# esp_thermometer.net
KiCad netlist of a schematic drawn in EAGLE
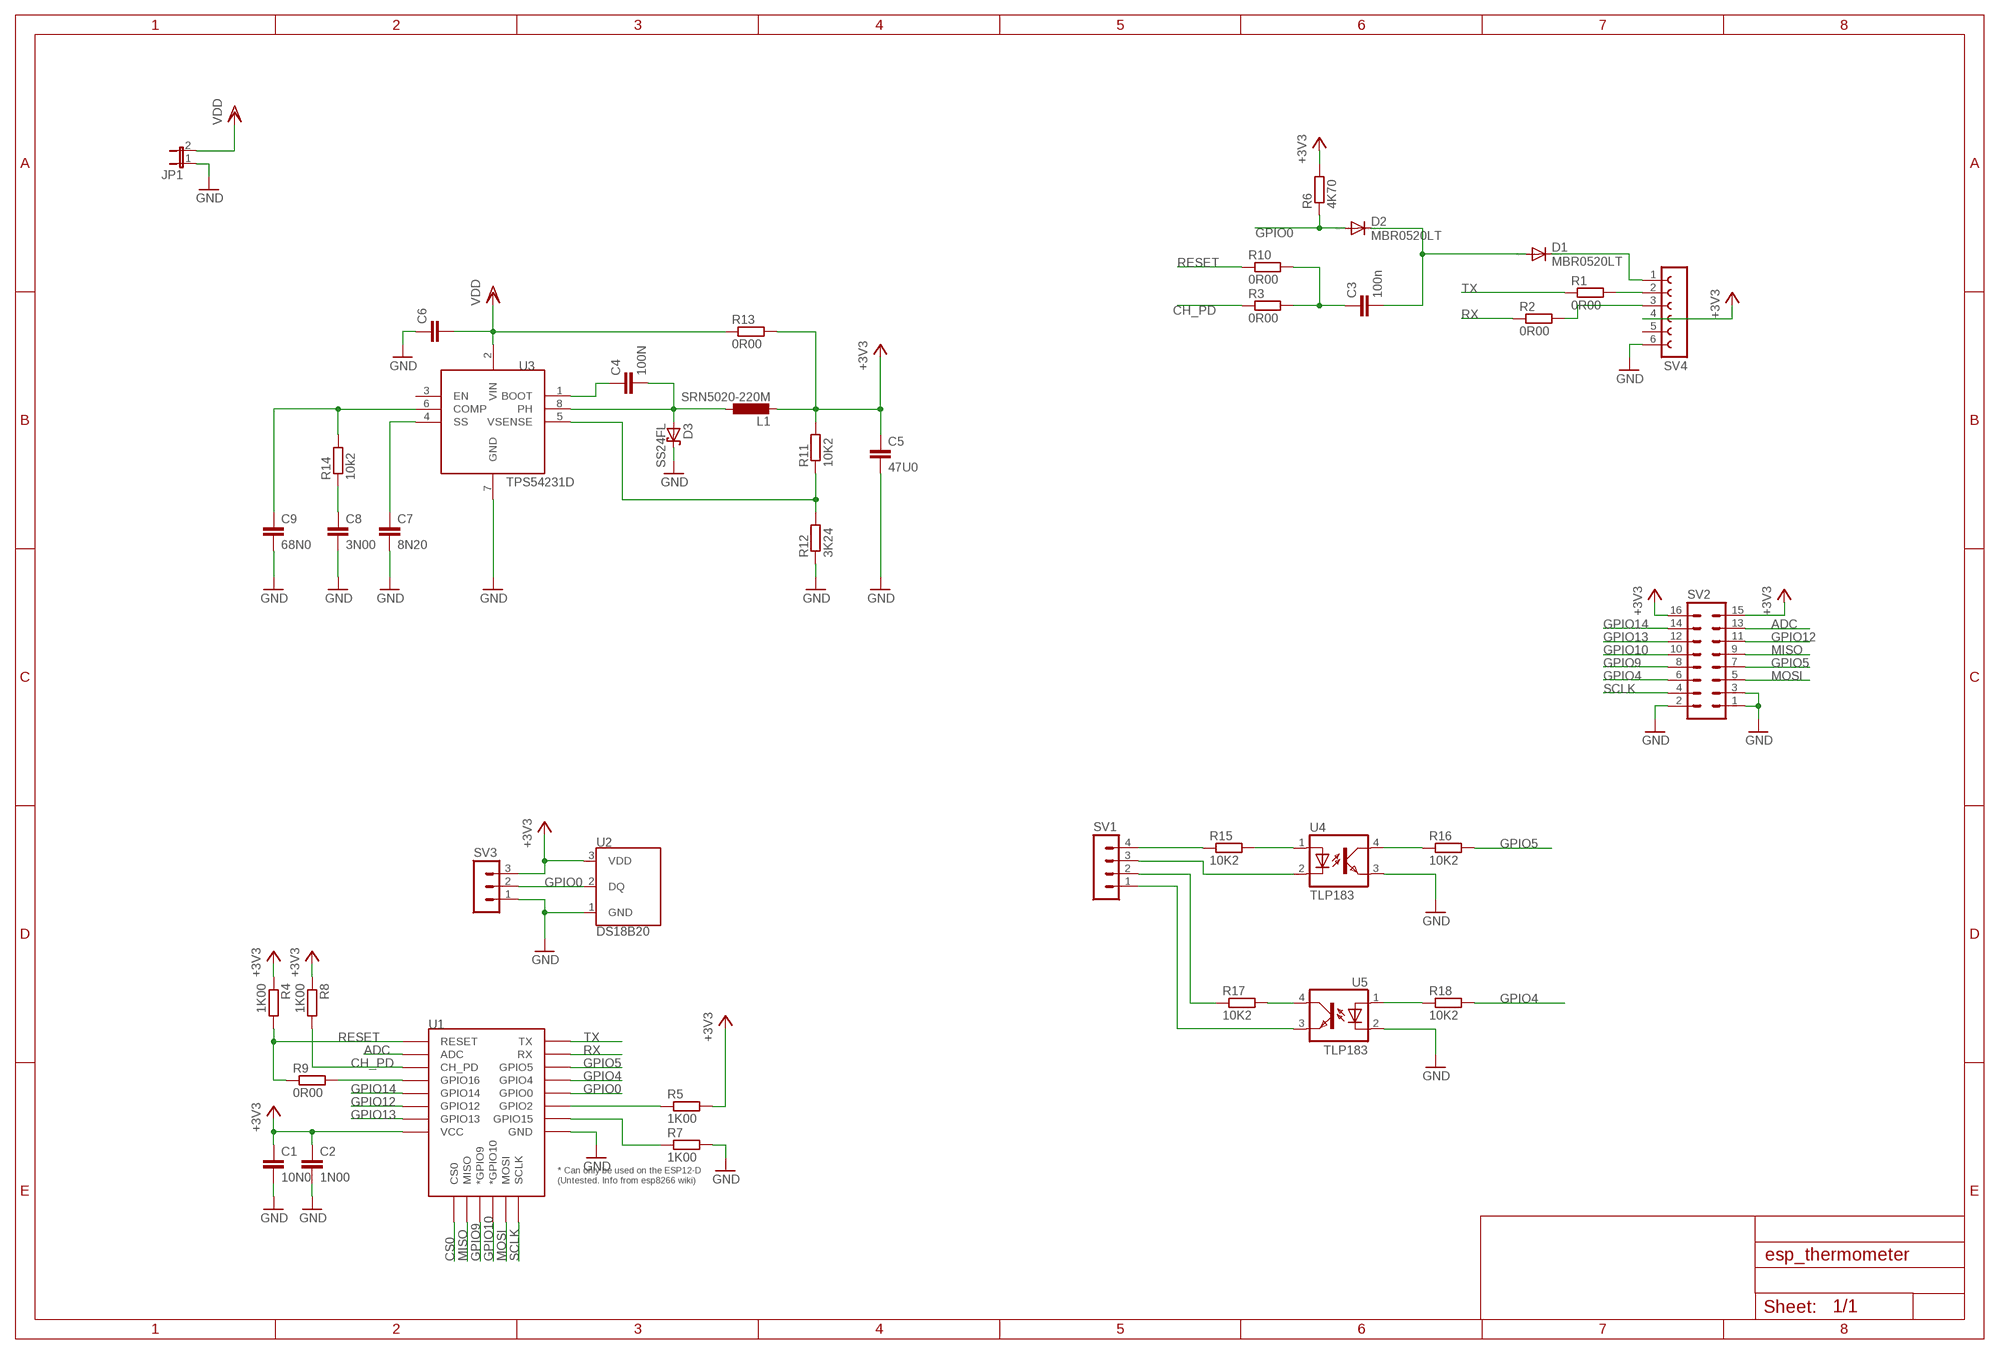
[diagram p0: schematic, sheet 1]

(export (version "E")
  (design (tool "Eeschema 10.0.6"))
  (components
    (comp (ref "C1")
      (value "10N0")
      (footprint "eagle-import:C1206K")
      (libsource (lib "eagle-import") (part "C-EUC1206K"))
    )
    (comp (ref "C2")
      (value "1N00")
      (footprint "eagle-import:C1206K")
      (libsource (lib "eagle-import") (part "C-EUC1206K"))
    )
    (comp (ref "C3")
      (value "100n")
      (footprint "eagle-import:C1206K")
      (libsource (lib "eagle-import") (part "C-EUC1206K"))
    )
    (comp (ref "C4")
      (value "100N")
      (footprint "eagle-import:C0805")
      (libsource (lib "eagle-import") (part "C-EUC0805"))
    )
    (comp (ref "C5")
      (value "47U0")
      (footprint "eagle-import:C1210")
      (libsource (lib "eagle-import") (part "C-EUC1210"))
    )
    (comp (ref "C6")
      (value "C-EUC1210")
      (footprint "eagle-import:C1210")
      (libsource (lib "eagle-import") (part "C-EUC1210"))
    )
    (comp (ref "C7")
      (value "8N20")
      (footprint "eagle-import:C0805")
      (libsource (lib "eagle-import") (part "C-EUC0805"))
    )
    (comp (ref "C8")
      (value "3N00")
      (footprint "eagle-import:C0805")
      (libsource (lib "eagle-import") (part "C-EUC0805"))
    )
    (comp (ref "C9")
      (value "68N0")
      (footprint "eagle-import:C0805")
      (libsource (lib "eagle-import") (part "C-EUC0805"))
    )
    (comp (ref "D1")
      (value "MBR0520LT")
      (footprint "eagle-import:SOD123")
      (libsource (lib "eagle-import") (part "MBR0520LT"))
    )
    (comp (ref "D2")
      (value "MBR0520LT")
      (footprint "eagle-import:SOD123")
      (libsource (lib "eagle-import") (part "MBR0520LT"))
    )
    (comp (ref "D3")
      (value "SS24FL")
      (footprint "eagle-import:SOD-123_MINI-SMA")
      (libsource (lib "eagle-import") (part "SS24FL"))
    )
    (comp (ref "JP1")
      (value "JP1E")
      (footprint "eagle-import:JP1")
      (libsource (lib "eagle-import") (part "JP1E"))
    )
    (comp (ref "L1")
      (value "SRN5020-220M")
      (footprint "eagle-import:L5050")
      (libsource (lib "eagle-import") (part "SRN5020-220M"))
    )
    (comp (ref "R1")
      (value "0R00")
      (footprint "eagle-import:R0805")
      (libsource (lib "eagle-import") (part "R-EU_R0805"))
    )
    (comp (ref "R2")
      (value "0R00")
      (footprint "eagle-import:R0805")
      (libsource (lib "eagle-import") (part "R-EU_R0805"))
    )
    (comp (ref "R3")
      (value "0R00")
      (footprint "eagle-import:R0805")
      (libsource (lib "eagle-import") (part "R-EU_R0805"))
    )
    (comp (ref "R4")
      (value "1K00")
      (footprint "eagle-import:R0805")
      (libsource (lib "eagle-import") (part "R-EU_R0805"))
    )
    (comp (ref "R5")
      (value "1K00")
      (footprint "eagle-import:R0805")
      (libsource (lib "eagle-import") (part "R-EU_R0805"))
    )
    (comp (ref "R6")
      (value "4K70")
      (footprint "eagle-import:R0805")
      (libsource (lib "eagle-import") (part "R-EU_R0805"))
    )
    (comp (ref "R7")
      (value "1K00")
      (footprint "eagle-import:R0805")
      (libsource (lib "eagle-import") (part "R-EU_R0805"))
    )
    (comp (ref "R8")
      (value "1K00")
      (footprint "eagle-import:R0805")
      (libsource (lib "eagle-import") (part "R-EU_R0805"))
    )
    (comp (ref "R9")
      (value "0R00")
      (footprint "eagle-import:R0805")
      (libsource (lib "eagle-import") (part "R-EU_R0805"))
    )
    (comp (ref "R10")
      (value "0R00")
      (footprint "eagle-import:R0805")
      (libsource (lib "eagle-import") (part "R-EU_R0805"))
    )
    (comp (ref "R11")
      (value "10K2")
      (footprint "eagle-import:R0805")
      (libsource (lib "eagle-import") (part "R-EU_R0805"))
    )
    (comp (ref "R12")
      (value "3K24")
      (footprint "eagle-import:R0805")
      (libsource (lib "eagle-import") (part "R-EU_R0805"))
    )
    (comp (ref "R13")
      (value "0R00")
      (footprint "eagle-import:R0805")
      (libsource (lib "eagle-import") (part "R-EU_R0805"))
    )
    (comp (ref "R14")
      (value "10k2")
      (footprint "eagle-import:R0805")
      (libsource (lib "eagle-import") (part "R-EU_R0805"))
    )
    (comp (ref "R15")
      (value "10K2")
      (footprint "eagle-import:R0805")
      (libsource (lib "eagle-import") (part "R-EU_R0805"))
    )
    (comp (ref "R16")
      (value "10K2")
      (footprint "eagle-import:R0805")
      (libsource (lib "eagle-import") (part "R-EU_R0805"))
    )
    (comp (ref "R17")
      (value "10K2")
      (footprint "eagle-import:R0805")
      (libsource (lib "eagle-import") (part "R-EU_R0805"))
    )
    (comp (ref "R18")
      (value "10K2")
      (footprint "eagle-import:R0805")
      (libsource (lib "eagle-import") (part "R-EU_R0805"))
    )
    (comp (ref "SV1")
      (value "MA04-1")
      (footprint "eagle-import:MA04-1")
      (libsource (lib "eagle-import") (part "MA04-1"))
    )
    (comp (ref "SV2")
      (value "MA08-2")
      (footprint "eagle-import:MA08-2")
      (libsource (lib "eagle-import") (part "MA08-2"))
    )
    (comp (ref "SV3")
      (value "MA03-1")
      (footprint "eagle-import:MA03-1")
      (libsource (lib "eagle-import") (part "MA03-1"))
    )
    (comp (ref "SV4")
      (value "FE06-1")
      (footprint "eagle-import:FE06")
      (libsource (lib "eagle-import") (part "FE06-1"))
    )
    (comp (ref "U1")
      (value "ESP12ESMD")
      (footprint "eagle-import:ESP12E-SMD")
      (libsource (lib "eagle-import") (part "ESP12ESMD"))
    )
    (comp (ref "U2")
      (value "DS18B20")
      (footprint "eagle-import:TO-92-AMMO")
      (libsource (lib "eagle-import") (part "DS18B20"))
    )
    (comp (ref "U3")
      (value "TPS54231D")
      (footprint "eagle-import:D0008A")
      (libsource (lib "eagle-import") (part "TPS54231D"))
    )
    (comp (ref "U4")
      (value "TLP183")
      (footprint "eagle-import:MINI-FLAT-4")
      (libsource (lib "eagle-import") (part "TLP183"))
    )
    (comp (ref "U5")
      (value "TLP183")
      (footprint "eagle-import:MINI-FLAT-4")
      (libsource (lib "eagle-import") (part "TLP183"))
    )
  )
  (nets
    (net (code "1") (name "+3V3") (class "Default")
      (node (ref "C1") (pin "1") (pinfunction "1_1") (pintype "passive"))
      (node (ref "C2") (pin "1") (pinfunction "1_1") (pintype "passive"))
      (node (ref "C5") (pin "1") (pinfunction "1_1") (pintype "passive"))
      (node (ref "L1") (pin "2") (pinfunction "2_2") (pintype "passive"))
      (node (ref "R11") (pin "2") (pinfunction "2_2") (pintype "passive"))
      (node (ref "R13") (pin "2") (pinfunction "2_2") (pintype "passive"))
      (node (ref "R4") (pin "1") (pinfunction "1_1") (pintype "passive"))
      (node (ref "R5") (pin "2") (pinfunction "2_2") (pintype "passive"))
      (node (ref "R6") (pin "2") (pinfunction "2_2") (pintype "passive"))
      (node (ref "R8") (pin "1") (pinfunction "1_1") (pintype "passive"))
      (node (ref "SV2") (pin "15") (pinfunction "15_15") (pintype "passive"))
      (node (ref "SV2") (pin "16") (pinfunction "16_16") (pintype "passive"))
      (node (ref "SV3") (pin "3") (pinfunction "3_3") (pintype "passive"))
      (node (ref "SV4") (pin "4") (pinfunction "4_4") (pintype "passive"))
      (node (ref "U1") (pin "VCC") (pinfunction "VCC_VCC") (pintype "bidirectional"))
      (node (ref "U2") (pin "3") (pinfunction "VDD_3") (pintype "power_in"))
    )
    (net (code "2") (name "/ADC") (class "Default")
      (node (ref "SV2") (pin "13") (pinfunction "13_13") (pintype "passive"))
      (node (ref "U1") (pin "ADC") (pinfunction "ADC_ADC") (pintype "bidirectional"))
    )
    (net (code "3") (name "/CH_PD") (class "Default")
      (node (ref "R3") (pin "1") (pinfunction "1_1") (pintype "passive"))
      (node (ref "R8") (pin "2") (pinfunction "2_2") (pintype "passive"))
      (node (ref "U1") (pin "CH_PD") (pinfunction "CH_PD_CH_PD") (pintype "bidirectional"))
    )
    (net (code "4") (name "/CS0") (class "Default")
      (node (ref "U1") (pin "CS0") (pinfunction "CS0_CS0") (pintype "bidirectional"))
    )
    (net (code "5") (name "/GPIO0") (class "Default")
      (node (ref "D2") (pin "A") (pinfunction "A_A") (pintype "passive"))
      (node (ref "R6") (pin "1") (pinfunction "1_1") (pintype "passive"))
      (node (ref "SV3") (pin "2") (pinfunction "2_2") (pintype "passive"))
      (node (ref "U1") (pin "GPIO0") (pinfunction "GPIO0_GPIO0") (pintype "bidirectional"))
      (node (ref "U2") (pin "2") (pinfunction "DQ_2") (pintype "bidirectional"))
    )
    (net (code "6") (name "/GPIO4") (class "Default")
      (node (ref "R18") (pin "2") (pinfunction "2_2") (pintype "passive"))
      (node (ref "SV2") (pin "6") (pinfunction "6_6") (pintype "passive"))
      (node (ref "U1") (pin "GPIO4") (pinfunction "GPIO4_GPIO4") (pintype "bidirectional"))
    )
    (net (code "7") (name "/GPIO5") (class "Default")
      (node (ref "R16") (pin "2") (pinfunction "2_2") (pintype "passive"))
      (node (ref "SV2") (pin "7") (pinfunction "7_7") (pintype "passive"))
      (node (ref "U1") (pin "GPIO5") (pinfunction "GPIO5_GPIO5") (pintype "bidirectional"))
    )
    (net (code "8") (name "/GPIO9") (class "Default")
      (node (ref "SV2") (pin "8") (pinfunction "8_8") (pintype "passive"))
      (node (ref "U1") (pin "GPIO9") (pinfunction "*GPIO9_GPIO9") (pintype "bidirectional"))
    )
    (net (code "9") (name "/GPIO10") (class "Default")
      (node (ref "SV2") (pin "10") (pinfunction "10_10") (pintype "passive"))
      (node (ref "U1") (pin "GPIO10") (pinfunction "*GPIO10_GPIO10") (pintype "bidirectional"))
    )
    (net (code "10") (name "/GPIO12") (class "Default")
      (node (ref "SV2") (pin "11") (pinfunction "11_11") (pintype "passive"))
      (node (ref "U1") (pin "GPIO12") (pinfunction "GPIO12_GPIO12") (pintype "bidirectional"))
    )
    (net (code "11") (name "/GPIO13") (class "Default")
      (node (ref "SV2") (pin "12") (pinfunction "12_12") (pintype "passive"))
      (node (ref "U1") (pin "GPIO13") (pinfunction "GPIO13_GPIO13") (pintype "bidirectional"))
    )
    (net (code "12") (name "/GPIO14") (class "Default")
      (node (ref "SV2") (pin "14") (pinfunction "14_14") (pintype "passive"))
      (node (ref "U1") (pin "GPIO14") (pinfunction "GPIO14_GPIO14") (pintype "bidirectional"))
    )
    (net (code "13") (name "/MISO") (class "Default")
      (node (ref "SV2") (pin "9") (pinfunction "9_9") (pintype "passive"))
      (node (ref "U1") (pin "MISO") (pinfunction "MISO_MISO") (pintype "bidirectional"))
    )
    (net (code "14") (name "/MOSI") (class "Default")
      (node (ref "SV2") (pin "5") (pinfunction "5_5") (pintype "passive"))
      (node (ref "U1") (pin "MOSI") (pinfunction "MOSI_MOSI") (pintype "bidirectional"))
    )
    (net (code "15") (name "/RESET") (class "Default")
      (node (ref "R10") (pin "1") (pinfunction "1_1") (pintype "passive"))
      (node (ref "R4") (pin "2") (pinfunction "2_2") (pintype "passive"))
      (node (ref "R9") (pin "1") (pinfunction "1_1") (pintype "passive"))
      (node (ref "U1") (pin "RESET") (pinfunction "RESET_RESET") (pintype "bidirectional"))
    )
    (net (code "16") (name "/RX") (class "Default")
      (node (ref "R2") (pin "1") (pinfunction "1_1") (pintype "passive"))
      (node (ref "U1") (pin "RXD0") (pinfunction "RX_RXD0") (pintype "bidirectional"))
    )
    (net (code "17") (name "/SCLK") (class "Default")
      (node (ref "SV2") (pin "4") (pinfunction "4_4") (pintype "passive"))
      (node (ref "U1") (pin "SCLK") (pinfunction "SCLK_SCLK") (pintype "bidirectional"))
    )
    (net (code "18") (name "/TX") (class "Default")
      (node (ref "R1") (pin "1") (pinfunction "1_1") (pintype "passive"))
      (node (ref "U1") (pin "TXD0") (pinfunction "TX_TXD0") (pintype "bidirectional"))
    )
    (net (code "19") (name "GND") (class "Default")
      (node (ref "C1") (pin "2") (pinfunction "2_2") (pintype "passive"))
      (node (ref "C2") (pin "2") (pinfunction "2_2") (pintype "passive"))
      (node (ref "C5") (pin "2") (pinfunction "2_2") (pintype "passive"))
      (node (ref "C6") (pin "1") (pinfunction "1_1") (pintype "passive"))
      (node (ref "C7") (pin "2") (pinfunction "2_2") (pintype "passive"))
      (node (ref "C8") (pin "2") (pinfunction "2_2") (pintype "passive"))
      (node (ref "C9") (pin "2") (pinfunction "2_2") (pintype "passive"))
      (node (ref "D3") (pin "C") (pinfunction "C_C") (pintype "passive"))
      (node (ref "JP1") (pin "1") (pinfunction "1_1") (pintype "passive"))
      (node (ref "R12") (pin "1") (pinfunction "1_1") (pintype "passive"))
      (node (ref "R7") (pin "2") (pinfunction "2_2") (pintype "passive"))
      (node (ref "SV2") (pin "1") (pinfunction "1_1") (pintype "passive"))
      (node (ref "SV2") (pin "2") (pinfunction "2_2") (pintype "passive"))
      (node (ref "SV2") (pin "3") (pinfunction "3_3") (pintype "passive"))
      (node (ref "SV3") (pin "1") (pinfunction "1_1") (pintype "passive"))
      (node (ref "SV4") (pin "6") (pinfunction "6_6") (pintype "passive"))
      (node (ref "U1") (pin "GND") (pinfunction "GND_GND") (pintype "bidirectional"))
      (node (ref "U2") (pin "1") (pinfunction "GND_1") (pintype "power_in"))
      (node (ref "U3") (pin "7") (pinfunction "GND_7") (pintype "power_in"))
      (node (ref "U4") (pin "3") (pinfunction "EMIT_3") (pintype "passive"))
      (node (ref "U5") (pin "2") (pinfunction "C_2") (pintype "passive"))
    )
    (net (code "20") (name "Net-(C3-Pad1)") (class "Default")
      (node (ref "C3") (pin "1") (pinfunction "1_1") (pintype "passive"))
      (node (ref "R10") (pin "2") (pinfunction "2_2") (pintype "passive"))
      (node (ref "R3") (pin "2") (pinfunction "2_2") (pintype "passive"))
    )
    (net (code "21") (name "Net-(C3-Pad2)") (class "Default")
      (node (ref "C3") (pin "2") (pinfunction "2_2") (pintype "passive"))
      (node (ref "D1") (pin "A") (pinfunction "A_A") (pintype "passive"))
      (node (ref "D2") (pin "C") (pinfunction "C_C") (pintype "passive"))
    )
    (net (code "22") (name "Net-(C8-Pad1)") (class "Default")
      (node (ref "C8") (pin "1") (pinfunction "1_1") (pintype "passive"))
      (node (ref "R14") (pin "1") (pinfunction "1_1") (pintype "passive"))
    )
    (net (code "23") (name "Net-(D1-PadC)") (class "Default")
      (node (ref "D1") (pin "C") (pinfunction "C_C") (pintype "passive"))
      (node (ref "SV4") (pin "1") (pinfunction "1_1") (pintype "passive"))
    )
    (net (code "24") (name "Net-(R1-Pad2)") (class "Default")
      (node (ref "R1") (pin "2") (pinfunction "2_2") (pintype "passive"))
      (node (ref "SV4") (pin "2") (pinfunction "2_2") (pintype "passive"))
    )
    (net (code "25") (name "Net-(R2-Pad2)") (class "Default")
      (node (ref "R2") (pin "2") (pinfunction "2_2") (pintype "passive"))
      (node (ref "SV4") (pin "3") (pinfunction "3_3") (pintype "passive"))
    )
    (net (code "26") (name "Net-(R5-Pad1)") (class "Default")
      (node (ref "R5") (pin "1") (pinfunction "1_1") (pintype "passive"))
      (node (ref "U1") (pin "GPIO2") (pinfunction "GPIO2_GPIO2") (pintype "bidirectional"))
    )
    (net (code "27") (name "Net-(R7-Pad1)") (class "Default")
      (node (ref "R7") (pin "1") (pinfunction "1_1") (pintype "passive"))
      (node (ref "U1") (pin "GPIO15") (pinfunction "GPIO15_GPIO15") (pintype "bidirectional"))
    )
    (net (code "28") (name "Net-(R9-Pad2)") (class "Default")
      (node (ref "R9") (pin "2") (pinfunction "2_2") (pintype "passive"))
      (node (ref "U1") (pin "GPIO16") (pinfunction "GPIO16_GPIO16") (pintype "bidirectional"))
    )
    (net (code "29") (name "Net-(R15-Pad1)") (class "Default")
      (node (ref "R15") (pin "1") (pinfunction "1_1") (pintype "passive"))
      (node (ref "SV1") (pin "4") (pinfunction "4_4") (pintype "passive"))
    )
    (net (code "30") (name "Net-(R17-Pad1)") (class "Default")
      (node (ref "R17") (pin "1") (pinfunction "1_1") (pintype "passive"))
      (node (ref "SV1") (pin "2") (pinfunction "2_2") (pintype "passive"))
    )
    (net (code "31") (name "Net-(U3-BOOT)") (class "Default")
      (node (ref "C4") (pin "1") (pinfunction "1_1") (pintype "passive"))
      (node (ref "U3") (pin "1") (pinfunction "BOOT_1") (pintype "bidirectional"))
    )
    (net (code "32") (name "Net-(U3-COMP)") (class "Default")
      (node (ref "C9") (pin "1") (pinfunction "1_1") (pintype "passive"))
      (node (ref "R14") (pin "2") (pinfunction "2_2") (pintype "passive"))
      (node (ref "U3") (pin "6") (pinfunction "COMP_6") (pintype "bidirectional"))
    )
    (net (code "33") (name "Net-(U3-PH)") (class "Default")
      (node (ref "C4") (pin "2") (pinfunction "2_2") (pintype "passive"))
      (node (ref "D3") (pin "A") (pinfunction "A_A") (pintype "passive"))
      (node (ref "L1") (pin "1") (pinfunction "1_1") (pintype "passive"))
      (node (ref "U3") (pin "8") (pinfunction "PH_8") (pintype "output"))
    )
    (net (code "34") (name "Net-(U3-SS)") (class "Default")
      (node (ref "C7") (pin "1") (pinfunction "1_1") (pintype "passive"))
      (node (ref "U3") (pin "4") (pinfunction "SS_4") (pintype "bidirectional"))
    )
    (net (code "35") (name "Net-(U3-VSENSE)") (class "Default")
      (node (ref "R11") (pin "1") (pinfunction "1_1") (pintype "passive"))
      (node (ref "R12") (pin "2") (pinfunction "2_2") (pintype "passive"))
      (node (ref "U3") (pin "5") (pinfunction "VSENSE_5") (pintype "input"))
    )
    (net (code "36") (name "Net-(U4-A)") (class "Default")
      (node (ref "R15") (pin "2") (pinfunction "2_2") (pintype "passive"))
      (node (ref "U4") (pin "1") (pinfunction "A_1") (pintype "passive"))
    )
    (net (code "37") (name "Net-(U4-C)") (class "Default")
      (node (ref "SV1") (pin "3") (pinfunction "3_3") (pintype "passive"))
      (node (ref "U4") (pin "2") (pinfunction "C_2") (pintype "passive"))
    )
    (net (code "38") (name "Net-(U4-COL)") (class "Default")
      (node (ref "R16") (pin "1") (pinfunction "1_1") (pintype "passive"))
      (node (ref "U4") (pin "4") (pinfunction "COL_4") (pintype "passive"))
    )
    (net (code "39") (name "Net-(U5-A)") (class "Default")
      (node (ref "R18") (pin "1") (pinfunction "1_1") (pintype "passive"))
      (node (ref "U5") (pin "1") (pinfunction "A_1") (pintype "passive"))
    )
    (net (code "40") (name "Net-(U5-COL)") (class "Default")
      (node (ref "R17") (pin "2") (pinfunction "2_2") (pintype "passive"))
      (node (ref "U5") (pin "4") (pinfunction "COL_4") (pintype "passive"))
    )
    (net (code "41") (name "Net-(U5-EMIT)") (class "Default")
      (node (ref "SV1") (pin "1") (pinfunction "1_1") (pintype "passive"))
      (node (ref "U5") (pin "3") (pinfunction "EMIT_3") (pintype "passive"))
    )
    (net (code "42") (name "VDD") (class "Default")
      (node (ref "C6") (pin "2") (pinfunction "2_2") (pintype "passive"))
      (node (ref "JP1") (pin "2") (pinfunction "2_2") (pintype "passive"))
      (node (ref "R13") (pin "1") (pinfunction "1_1") (pintype "passive"))
      (node (ref "U3") (pin "2") (pinfunction "VIN_2") (pintype "power_in"))
    )
    (net (code "43") (name "unconnected-(SV4-Pad5)") (class "Default")
      (node (ref "SV4") (pin "5") (pinfunction "5_5") (pintype "passive"))
    )
    (net (code "44") (name "unconnected-(U3-EN-Pad3)") (class "Default")
      (node (ref "U3") (pin "3") (pinfunction "EN_3") (pintype "input"))
    )
  )
)
